# LV8548MC_-V1_0.net
KiCad netlist of a schematic drawn in Altium Designer
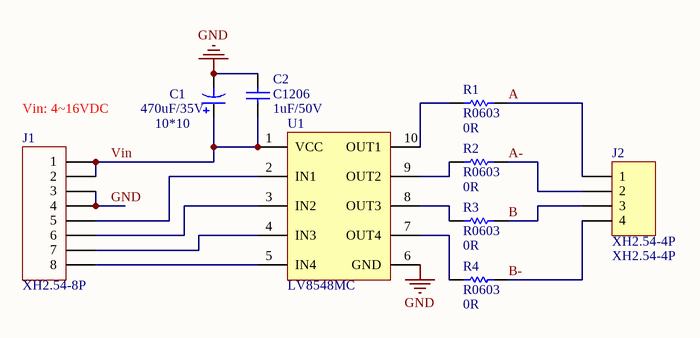
[diagram p0: LV8548MC测试板-V1.0.SchDoc]

(export (version "E")
  (design (tool "Eeschema 10.0.6"))
  (components
    (comp (ref "C1")
      (value "470uF/35V")
      (footprint "CAP_SO_10*10")
      (description "Polarized Capacitor (Surface Mount)")
      (fields (field (name "ALTIUM_VALUE") "10*10") (field (name "PUBLISHER") "Altium Limited"))
      (libsource (lib "Miscellaneous Devices") (part "Cap Pol3"))
    )
    (comp (ref "C2")
      (value "C1206")
      (footprint "1206")
      (description "Capacitor")
      (fields (field (name "ALTIUM_VALUE") "1uF/50V") (field (name "PUBLISHER") "Altium Limited"))
      (libsource (lib "Miscellaneous Devices") (part "Cap"))
    )
    (comp (ref "J1")
      (value "XH2.54-8P")
      (footprint "XH2.54-8")
      (description "Header, 6-Pin")
      (fields (field (name "Comment") "PH2.0-8P") (field (name "PUBLISHER") "Altium Limited"))
      (libsource (lib "SCH") (part "PH2.0-8P"))
    )
    (comp (ref "J2")
      (value "XH2.54-4P")
      (footprint "XH2.54-4")
      (description "Header, 4-Pin")
      (fields (field (name "ALTIUM_VALUE") "XH2.54-4P") (field (name "PUBLISHER") "Altium Limited"))
      (libsource (lib "Miscellaneous Connectors") (part "Header 4"))
    )
    (comp (ref "R1")
      (value "R0603")
      (footprint "0603")
      (description "Resistor")
      (fields (field (name "ALTIUM_VALUE") "0R") (field (name "PUBLISHER") "Altium Limited"))
      (libsource (lib "Miscellaneous Devices") (part "Res1"))
    )
    (comp (ref "R2")
      (value "R0603")
      (footprint "0603")
      (description "Resistor")
      (fields (field (name "ALTIUM_VALUE") "0R") (field (name "PUBLISHER") "Altium Limited"))
      (libsource (lib "Miscellaneous Devices") (part "Res1"))
    )
    (comp (ref "R3")
      (value "R0603")
      (footprint "0603")
      (description "Resistor")
      (fields (field (name "ALTIUM_VALUE") "0R") (field (name "PUBLISHER") "Altium Limited"))
      (libsource (lib "Miscellaneous Devices") (part "Res1"))
    )
    (comp (ref "R4")
      (value "R0603")
      (footprint "0603")
      (description "Resistor")
      (fields (field (name "ALTIUM_VALUE") "0R") (field (name "PUBLISHER") "Altium Limited"))
      (libsource (lib "Miscellaneous Devices") (part "Res1"))
    )
    (comp (ref "U1") (value "LV8548MC") (footprint "SOIC10") (libsource (lib "SCH") (part "LV8548MC")))
  )
  (nets
    (net (code "1") (name "/A") (class "Default")
      (node (ref "J2") (pin "1") (pinfunction "1_1") (pintype "passive"))
      (node (ref "R1") (pin "1") (pinfunction "1_1") (pintype "passive"))
    )
    (net (code "2") (name "/A-") (class "Default")
      (node (ref "J2") (pin "2") (pinfunction "2_2") (pintype "passive"))
      (node (ref "R2") (pin "1") (pinfunction "1_1") (pintype "passive"))
    )
    (net (code "3") (name "/B") (class "Default")
      (node (ref "J2") (pin "3") (pinfunction "3_3") (pintype "passive"))
      (node (ref "R3") (pin "1") (pinfunction "1_1") (pintype "passive"))
    )
    (net (code "4") (name "/B-") (class "Default")
      (node (ref "J2") (pin "4") (pinfunction "4_4") (pintype "passive"))
      (node (ref "R4") (pin "1") (pinfunction "1_1") (pintype "passive"))
    )
    (net (code "5") (name "/Vin") (class "Default")
      (node (ref "C1") (pin "1") (pinfunction "1_1") (pintype "passive"))
      (node (ref "C2") (pin "1") (pinfunction "1_1") (pintype "passive"))
      (node (ref "J1") (pin "1") (pinfunction "1_1") (pintype "passive"))
      (node (ref "J1") (pin "2") (pinfunction "2_2") (pintype "passive"))
      (node (ref "U1") (pin "1") (pinfunction "VCC_1") (pintype "passive"))
    )
    (net (code "6") (name "GND") (class "Default")
      (node (ref "C1") (pin "2") (pinfunction "2_2") (pintype "passive"))
      (node (ref "C2") (pin "2") (pinfunction "2_2") (pintype "passive"))
      (node (ref "J1") (pin "3") (pinfunction "3_3") (pintype "passive"))
      (node (ref "J1") (pin "4") (pinfunction "4_4") (pintype "passive"))
      (node (ref "U1") (pin "6") (pinfunction "GND_6") (pintype "passive"))
    )
    (net (code "7") (name "Net-(U1-IN1)") (class "Default")
      (node (ref "J1") (pin "5") (pinfunction "5_5") (pintype "passive"))
      (node (ref "U1") (pin "2") (pinfunction "IN1_2") (pintype "passive"))
    )
    (net (code "8") (name "Net-(U1-IN2)") (class "Default")
      (node (ref "J1") (pin "6") (pinfunction "6_6") (pintype "passive"))
      (node (ref "U1") (pin "3") (pinfunction "IN2_3") (pintype "passive"))
    )
    (net (code "9") (name "Net-(U1-IN3)") (class "Default")
      (node (ref "J1") (pin "7") (pinfunction "7_7") (pintype "passive"))
      (node (ref "U1") (pin "4") (pinfunction "IN3_4") (pintype "passive"))
    )
    (net (code "10") (name "Net-(U1-IN4)") (class "Default")
      (node (ref "J1") (pin "8") (pinfunction "8_8") (pintype "passive"))
      (node (ref "U1") (pin "5") (pinfunction "IN4_5") (pintype "passive"))
    )
    (net (code "11") (name "Net-(U1-OUT1)") (class "Default")
      (node (ref "R1") (pin "2") (pinfunction "2_2") (pintype "passive"))
      (node (ref "U1") (pin "10") (pinfunction "OUT1_10") (pintype "passive"))
    )
    (net (code "12") (name "Net-(U1-OUT2)") (class "Default")
      (node (ref "R2") (pin "2") (pinfunction "2_2") (pintype "passive"))
      (node (ref "U1") (pin "9") (pinfunction "OUT2_9") (pintype "passive"))
    )
    (net (code "13") (name "Net-(U1-OUT3)") (class "Default")
      (node (ref "R3") (pin "2") (pinfunction "2_2") (pintype "passive"))
      (node (ref "U1") (pin "8") (pinfunction "OUT3_8") (pintype "passive"))
    )
    (net (code "14") (name "Net-(U1-OUT4)") (class "Default")
      (node (ref "R4") (pin "2") (pinfunction "2_2") (pintype "passive"))
      (node (ref "U1") (pin "7") (pinfunction "OUT4_7") (pintype "passive"))
    )
  )
)
